# v1.net
KiCad netlist of a schematic drawn in EAGLE
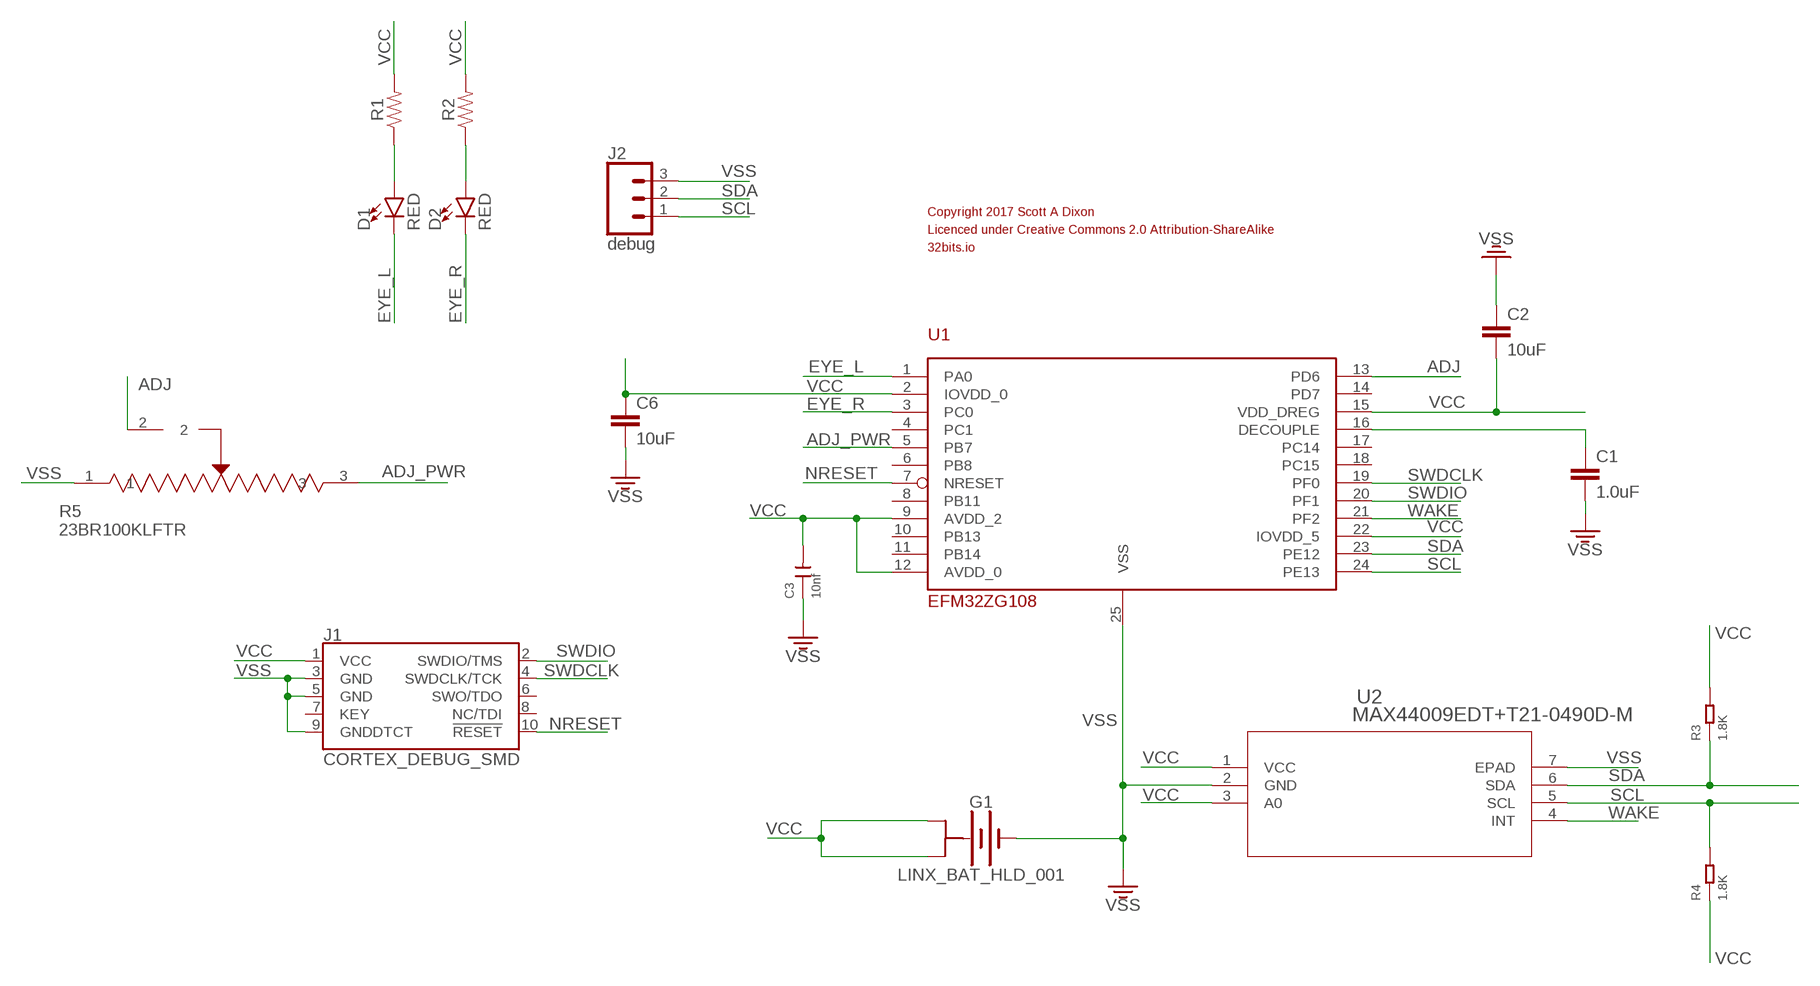
[diagram p0: schematic, sheet 1]

(export (version "E")
  (design (tool "Eeschema 10.0.6"))
  (components
    (comp (ref "C1")
      (value "1.0uF")
      (footprint "eagle-import:0603")
      (libsource (lib "eagle-import") (part "1.0UF-0603-16V-10%"))
    )
    (comp (ref "C2")
      (value "10uF")
      (footprint "eagle-import:0805")
      (libsource (lib "eagle-import") (part "10UF-0805-10V-10%"))
    )
    (comp (ref "C3")
      (value "10nf")
      (footprint "eagle-import:C0402")
      (fields (field (name "MPN") "CC0402KRX7R9BB103"))
      (libsource (lib "eagle-import") (part "CERAMIC-10NF-50V-10%-X7R(0402)"))
    )
    (comp (ref "C6")
      (value "10uF")
      (footprint "eagle-import:0805")
      (libsource (lib "eagle-import") (part "10UF-0805-10V-10%"))
    )
    (comp (ref "D1")
      (value "RED")
      (footprint "eagle-import:LED-1206")
      (libsource (lib "eagle-import") (part "LED-RED1206"))
    )
    (comp (ref "D2")
      (value "RED")
      (footprint "eagle-import:LED-1206")
      (libsource (lib "eagle-import") (part "LED-RED1206"))
    )
    (comp (ref "G1")
      (value "LINX_BAT_HLD_001")
      (footprint "eagle-import:BATT-RETAINER-20MM")
      (libsource (lib "eagle-import") (part "LINX_BAT_HLD_001"))
    )
    (comp (ref "J1")
      (value "CORTEX_DEBUG_SMD")
      (footprint "eagle-import:SAMTECH_FTSH-105-01")
      (libsource (lib "eagle-import") (part "CORTEX_DEBUG_SMD"))
    )
    (comp (ref "J2")
      (value "debug")
      (footprint "eagle-import:1X03")
      (libsource (lib "eagle-import") (part "CONN_03"))
    )
    (comp (ref "R1")
      (value "68OHM-0603-1/10W-1%")
      (footprint "eagle-import:0603")
      (libsource (lib "eagle-import") (part "68OHM-0603-1/10W-1%"))
    )
    (comp (ref "R2")
      (value "68OHM-0603-1/10W-1%")
      (footprint "eagle-import:0603")
      (libsource (lib "eagle-import") (part "68OHM-0603-1/10W-1%"))
    )
    (comp (ref "R3")
      (value "1.8K")
      (footprint "eagle-import:R0402")
      (fields (field (name "MPN") "RC0402JR-071KL"))
      (libsource (lib "eagle-import") (part "SMD-RES-1K-5%-1/16W(0402)"))
    )
    (comp (ref "R4")
      (value "1.8K")
      (footprint "eagle-import:R0402")
      (fields (field (name "MPN") "RC0402JR-071KL"))
      (libsource (lib "eagle-import") (part "SMD-RES-1K-5%-1/16W(0402)"))
    )
    (comp (ref "R5")
      (value "23BR100KLFTR")
      (footprint "eagle-import:SOT_23BR100KLFTR")
      (libsource (lib "eagle-import") (part "23BR100KLFTR"))
    )
    (comp (ref "U$1")
      (value "COPYRIGHT")
      (footprint "eagle-import:COPYRIGHT")
      (libsource (lib "eagle-import") (part "COPYRIGHT"))
    )
    (comp (ref "U1")
      (value "EFM32ZG108")
      (footprint "eagle-import:QFN-24")
      (libsource (lib "eagle-import") (part "EFM32ZG108"))
    )
    (comp (ref "U2")
      (value "MAX44009EDT+T21-0490D-M")
      (footprint "eagle-import:21-0490D-M")
      (fields (field (name "MANUFACTURER_PART_NUMBER") "MAX44009EDT+T"))
      (libsource (lib "eagle-import") (part "MAX44009EDT+T21-0490D-M"))
    )
  )
  (nets
    (net (code "1") (name "/ADJ") (class "Default")
      (node (ref "R5") (pin "2") (pinfunction "2_2") (pintype "passive"))
      (node (ref "U1") (pin "13") (pinfunction "PD6_13") (pintype "bidirectional"))
    )
    (net (code "2") (name "/ADJ_PWR") (class "Default")
      (node (ref "R5") (pin "3") (pinfunction "3_3") (pintype "passive"))
      (node (ref "U1") (pin "5") (pinfunction "PB7_5") (pintype "bidirectional"))
    )
    (net (code "3") (name "/EYE_L") (class "Default")
      (node (ref "D1") (pin "C") (pinfunction "C_C") (pintype "passive"))
      (node (ref "U1") (pin "1") (pinfunction "PA0_1") (pintype "bidirectional"))
    )
    (net (code "4") (name "/EYE_R") (class "Default")
      (node (ref "D2") (pin "C") (pinfunction "C_C") (pintype "passive"))
      (node (ref "U1") (pin "3") (pinfunction "PC0_3") (pintype "bidirectional"))
    )
    (net (code "5") (name "/NRESET") (class "Default")
      (node (ref "J1") (pin "10") (pinfunction "~{RESET}_10") (pintype "bidirectional"))
      (node (ref "U1") (pin "7") (pinfunction "NRESET_7") (pintype "input"))
    )
    (net (code "6") (name "/SCL") (class "Default")
      (node (ref "J2") (pin "1") (pinfunction "1_1") (pintype "passive"))
      (node (ref "R4") (pin "2") (pinfunction "2_2") (pintype "passive"))
      (node (ref "U1") (pin "24") (pinfunction "PE13_24") (pintype "bidirectional"))
      (node (ref "U2") (pin "5") (pinfunction "SCL_5") (pintype "passive"))
    )
    (net (code "7") (name "/SDA") (class "Default")
      (node (ref "J2") (pin "2") (pinfunction "2_2") (pintype "passive"))
      (node (ref "R3") (pin "1") (pinfunction "1_1") (pintype "passive"))
      (node (ref "U1") (pin "23") (pinfunction "PE12_23") (pintype "bidirectional"))
      (node (ref "U2") (pin "6") (pinfunction "SDA_6") (pintype "passive"))
    )
    (net (code "8") (name "/SWDCLK") (class "Default")
      (node (ref "J1") (pin "4") (pinfunction "SWDCLK/TCK_4") (pintype "bidirectional"))
      (node (ref "U1") (pin "19") (pinfunction "PF0_19") (pintype "bidirectional"))
    )
    (net (code "9") (name "/SWDIO") (class "Default")
      (node (ref "J1") (pin "2") (pinfunction "SWDIO/TMS_2") (pintype "bidirectional"))
      (node (ref "U1") (pin "20") (pinfunction "PF1_20") (pintype "bidirectional"))
    )
    (net (code "10") (name "/VCC") (class "Default")
      (node (ref "C2") (pin "2") (pinfunction "2_2") (pintype "passive"))
      (node (ref "C3") (pin "2") (pinfunction "2_2") (pintype "passive"))
      (node (ref "C6") (pin "1") (pinfunction "1_1") (pintype "passive"))
      (node (ref "G1") (pin "P$1") (pinfunction "+$1_P$1") (pintype "power_in"))
      (node (ref "G1") (pin "P$2") (pinfunction "+$1_P$2") (pintype "power_in"))
      (node (ref "G1") (pin "P$3") (pinfunction "+$2_P$3") (pintype "power_in"))
      (node (ref "G1") (pin "P$4") (pinfunction "+$2_P$4") (pintype "power_in"))
      (node (ref "J1") (pin "1") (pinfunction "VCC_1") (pintype "bidirectional"))
      (node (ref "R1") (pin "2") (pinfunction "2_2") (pintype "passive"))
      (node (ref "R2") (pin "2") (pinfunction "2_2") (pintype "passive"))
      (node (ref "R3") (pin "2") (pinfunction "2_2") (pintype "passive"))
      (node (ref "R4") (pin "1") (pinfunction "1_1") (pintype "passive"))
      (node (ref "U1") (pin "12") (pinfunction "AVDD_0_12") (pintype "power_in"))
      (node (ref "U1") (pin "15") (pinfunction "VDD_DREG_15") (pintype "power_in"))
      (node (ref "U1") (pin "2") (pinfunction "IOVDD_0_2") (pintype "power_in"))
      (node (ref "U1") (pin "22") (pinfunction "IOVDD_5_22") (pintype "power_in"))
      (node (ref "U1") (pin "9") (pinfunction "AVDD_2_9") (pintype "power_in"))
      (node (ref "U2") (pin "1") (pinfunction "VCC_1") (pintype "power_in"))
      (node (ref "U2") (pin "3") (pinfunction "A0_3") (pintype "passive"))
    )
    (net (code "11") (name "/WAKE") (class "Default")
      (node (ref "U1") (pin "21") (pinfunction "PF2_21") (pintype "bidirectional"))
      (node (ref "U2") (pin "4") (pinfunction "INT_4") (pintype "output"))
    )
    (net (code "12") (name "Net-(D1-PadA)") (class "Default")
      (node (ref "D1") (pin "A") (pinfunction "A_A") (pintype "passive"))
      (node (ref "R1") (pin "1") (pinfunction "1_1") (pintype "passive"))
    )
    (net (code "13") (name "Net-(D2-PadA)") (class "Default")
      (node (ref "D2") (pin "A") (pinfunction "A_A") (pintype "passive"))
      (node (ref "R2") (pin "1") (pinfunction "1_1") (pintype "passive"))
    )
    (net (code "14") (name "Net-(U1-DECOUPLE)") (class "Default")
      (node (ref "C1") (pin "1") (pinfunction "1_1") (pintype "passive"))
      (node (ref "U1") (pin "16") (pinfunction "DECOUPLE_16") (pintype "output"))
    )
    (net (code "15") (name "VSS") (class "Default")
      (node (ref "C1") (pin "2") (pinfunction "2_2") (pintype "passive"))
      (node (ref "C2") (pin "1") (pinfunction "1_1") (pintype "passive"))
      (node (ref "C3") (pin "1") (pinfunction "1_1") (pintype "passive"))
      (node (ref "C6") (pin "2") (pinfunction "2_2") (pintype "passive"))
      (node (ref "G1") (pin "P$0") (pinfunction "-_P$0") (pintype "power_in"))
      (node (ref "J1") (pin "3") (pinfunction "GND_3") (pintype "bidirectional"))
      (node (ref "J1") (pin "5") (pinfunction "GND_5") (pintype "bidirectional"))
      (node (ref "J1") (pin "9") (pinfunction "GNDDTCT_9") (pintype "bidirectional"))
      (node (ref "J2") (pin "3") (pinfunction "3_3") (pintype "passive"))
      (node (ref "R5") (pin "1") (pinfunction "1_1") (pintype "passive"))
      (node (ref "U1") (pin "25") (pinfunction "VSS_25") (pintype "power_in"))
      (node (ref "U2") (pin "2") (pinfunction "GND_2") (pintype "power_in"))
      (node (ref "U2") (pin "7") (pinfunction "EPAD_7") (pintype "passive"))
    )
    (net (code "16") (name "unconnected-(J1-KEY-Pad7)") (class "Default")
      (node (ref "J1") (pin "7") (pinfunction "KEY_7") (pintype "bidirectional"))
    )
    (net (code "17") (name "unconnected-(J1-NC{slash}TDI-Pad8)") (class "Default")
      (node (ref "J1") (pin "8") (pinfunction "NC/TDI_8") (pintype "bidirectional"))
    )
    (net (code "18") (name "unconnected-(J1-SWO{slash}TDO-Pad6)") (class "Default")
      (node (ref "J1") (pin "6") (pinfunction "SWO/TDO_6") (pintype "bidirectional"))
    )
    (net (code "19") (name "unconnected-(U1-PB8-Pad6)") (class "Default")
      (node (ref "U1") (pin "6") (pinfunction "PB8_6") (pintype "bidirectional"))
    )
    (net (code "20") (name "unconnected-(U1-PB11-Pad8)") (class "Default")
      (node (ref "U1") (pin "8") (pinfunction "PB11_8") (pintype "bidirectional"))
    )
    (net (code "21") (name "unconnected-(U1-PB13-Pad10)") (class "Default")
      (node (ref "U1") (pin "10") (pinfunction "PB13_10") (pintype "bidirectional"))
    )
    (net (code "22") (name "unconnected-(U1-PB14-Pad11)") (class "Default")
      (node (ref "U1") (pin "11") (pinfunction "PB14_11") (pintype "bidirectional"))
    )
    (net (code "23") (name "unconnected-(U1-PC1-Pad4)") (class "Default")
      (node (ref "U1") (pin "4") (pinfunction "PC1_4") (pintype "bidirectional"))
    )
    (net (code "24") (name "unconnected-(U1-PC14-Pad17)") (class "Default")
      (node (ref "U1") (pin "17") (pinfunction "PC14_17") (pintype "bidirectional"))
    )
    (net (code "25") (name "unconnected-(U1-PC15-Pad18)") (class "Default")
      (node (ref "U1") (pin "18") (pinfunction "PC15_18") (pintype "bidirectional"))
    )
    (net (code "26") (name "unconnected-(U1-PD7-Pad14)") (class "Default")
      (node (ref "U1") (pin "14") (pinfunction "PD7_14") (pintype "bidirectional"))
    )
  )
)
